# 16_-SP1_TYPEC_PWR_IN.net
KiCad netlist of a schematic drawn in Altium Designer
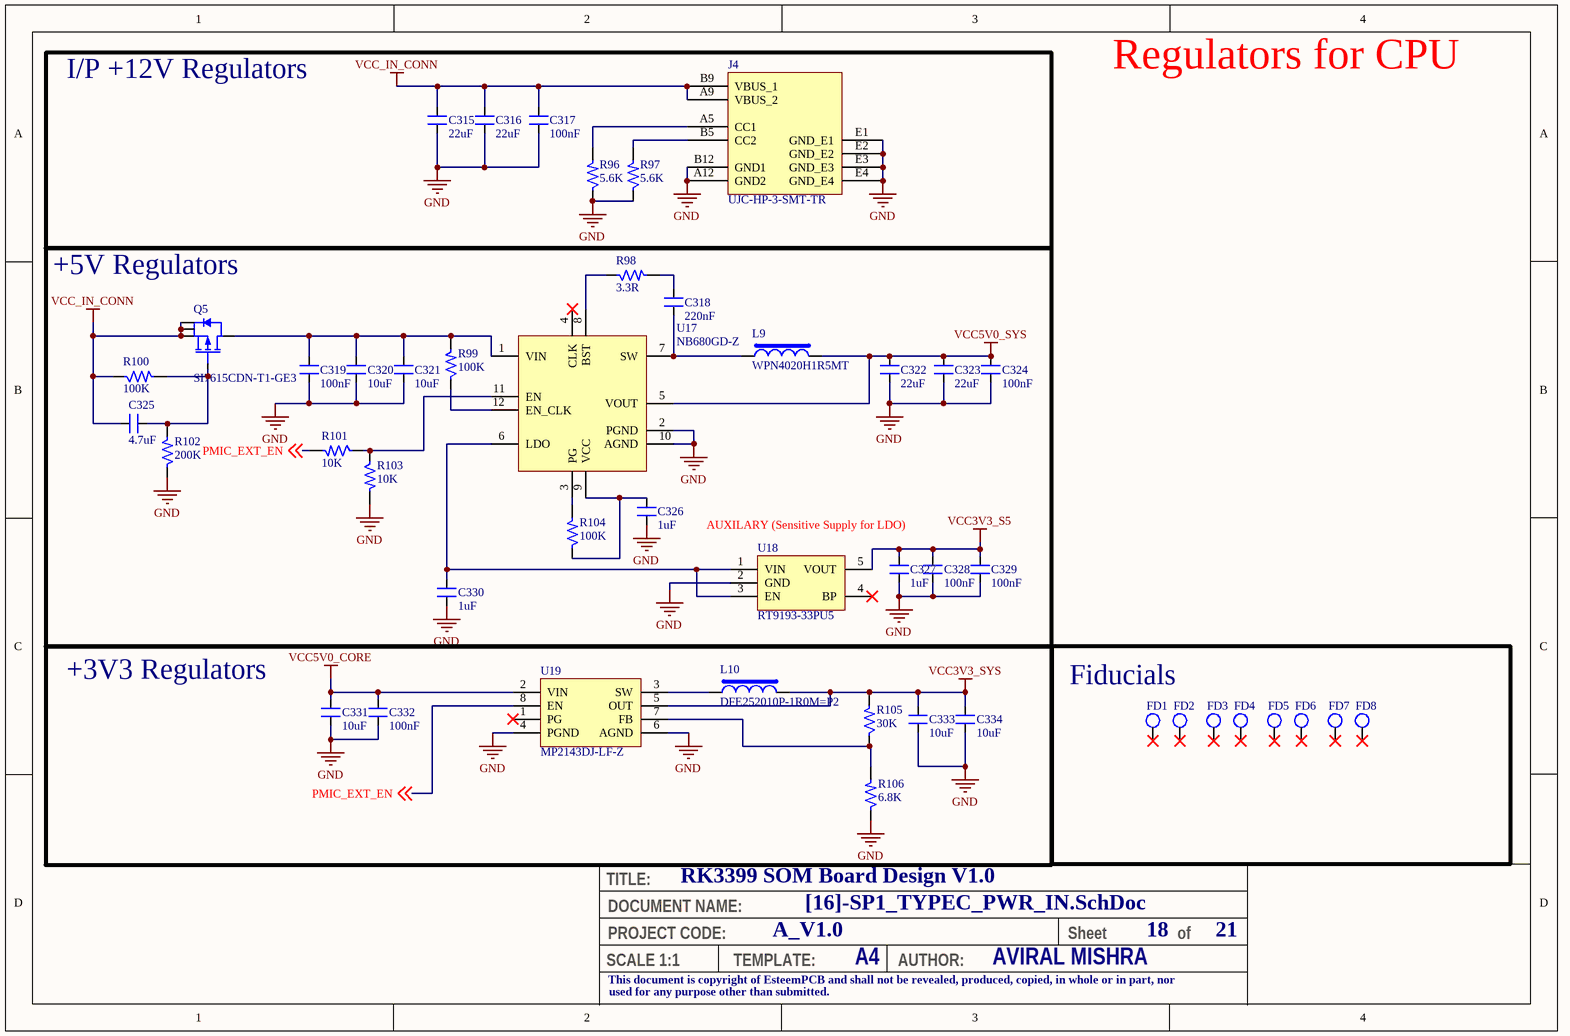
[diagram p0: [16]-SP1_TYPEC_PWR_IN.SchDoc]

(export (version "E")
  (design (tool "Eeschema 10.0.6"))
  (components
    (comp (ref "C315")
      (value "22uF")
      (footprint "CAP_0603")
      (description "22µF ±20% 10V Ceramic Capacitor X5R 0603 (1608 Metric)")
      (fields
        (field (name "MANUFACTURER") "Murata Electronics")
        (field (name "MANUFACTURER PART NUMBER") "GRM188R61A226ME15D")
      )
      (libsource (lib "RK3399 _Module_Schlib") (part "CAP_22uF-10V-20%-0603"))
    )
    (comp (ref "C316")
      (value "22uF")
      (footprint "CAP_0603")
      (description "22µF ±20% 10V Ceramic Capacitor X5R 0603 (1608 Metric)")
      (fields
        (field (name "MANUFACTURER") "Murata Electronics")
        (field (name "MANUFACTURER PART NUMBER") "GRM188R61A226ME15D")
      )
      (libsource (lib "RK3399 _Module_Schlib") (part "CAP_22uF-10V-20%-0603"))
    )
    (comp (ref "C317")
      (value "100nF")
      (footprint "CAP_0402")
      (description "0.1µF ±10% 25V Ceramic Capacitor X7R 0402 (1005 Metric)")
      (fields
        (field (name "MANUFACTURER") "Walsin Technology Corporation")
        (field (name "MANUFACTURER PART NUMBER") "0402B104K250CT")
      )
      (libsource (lib "RK3399 _Module_Schlib") (part "CAP_100nF-25V-10%-0402"))
    )
    (comp (ref "C318")
      (value "220nF")
      (footprint "CAP_0402")
      (description "0.22µF ±10% 10V Ceramic Capacitor X7R 0402 (1005 Metric)")
      (fields
        (field (name "MANUFACTURER") "Samsung Electro-Mechanics")
        (field (name "MANUFACTURER PART NUMBER") "CL05B224KP5NNNC")
      )
      (libsource (lib "RK3399 _Module_Schlib") (part "CAP_220nF-10V-10%-0402"))
    )
    (comp (ref "C319")
      (value "100nF")
      (footprint "CAP_0402")
      (description "0.1µF ±10% 25V Ceramic Capacitor X7R 0402 (1005 Metric)")
      (fields
        (field (name "MANUFACTURER") "Walsin Technology Corporation")
        (field (name "MANUFACTURER PART NUMBER") "0402B104K250CT")
      )
      (libsource (lib "RK3399 _Module_Schlib") (part "CAP_100nF-25V-10%-0402"))
    )
    (comp (ref "C320")
      (value "10uF")
      (footprint "CAP_0402")
      (description "10µF ±20% 10V Ceramic Capacitor X5R 0402 (1005 Metric)")
      (fields
        (field (name "MANUFACTURER PART NUMBER") "CL05A106MP5NUNC")
        (field (name "MANUFACTURER") "Samsung Electro-Mechanics")
      )
      (libsource (lib "RK3399 _Module_Schlib") (part "CAP_10uF-10V-20%-0402"))
    )
    (comp (ref "C321")
      (value "10uF")
      (footprint "CAP_0402")
      (description "10µF ±20% 10V Ceramic Capacitor X5R 0402 (1005 Metric)")
      (fields
        (field (name "MANUFACTURER PART NUMBER") "CL05A106MP5NUNC")
        (field (name "MANUFACTURER") "Samsung Electro-Mechanics")
      )
      (libsource (lib "RK3399 _Module_Schlib") (part "CAP_10uF-10V-20%-0402"))
    )
    (comp (ref "C322")
      (value "22uF")
      (footprint "CAP_0603")
      (description "22µF ±20% 10V Ceramic Capacitor X5R 0603 (1608 Metric)")
      (fields
        (field (name "MANUFACTURER") "Murata Electronics")
        (field (name "MANUFACTURER PART NUMBER") "GRM188R61A226ME15D")
      )
      (libsource (lib "RK3399 _Module_Schlib") (part "CAP_22uF-10V-20%-0603"))
    )
    (comp (ref "C323")
      (value "22uF")
      (footprint "CAP_0603")
      (description "22µF ±20% 10V Ceramic Capacitor X5R 0603 (1608 Metric)")
      (fields
        (field (name "MANUFACTURER") "Murata Electronics")
        (field (name "MANUFACTURER PART NUMBER") "GRM188R61A226ME15D")
      )
      (libsource (lib "RK3399 _Module_Schlib") (part "CAP_22uF-10V-20%-0603"))
    )
    (comp (ref "C324")
      (value "100nF")
      (footprint "CAP_0402")
      (description "0.1µF ±10% 25V Ceramic Capacitor X7R 0402 (1005 Metric)")
      (fields
        (field (name "MANUFACTURER") "Walsin Technology Corporation")
        (field (name "MANUFACTURER PART NUMBER") "0402B104K250CT")
      )
      (libsource (lib "RK3399 _Module_Schlib") (part "CAP_100nF-25V-10%-0402"))
    )
    (comp (ref "C325")
      (value "4.7uF")
      (footprint "CAP_0402")
      (description "4.7µF ±10% 10V Ceramic Capacitor X5R 0402 (1005 Metric)")
      (fields
        (field (name "MANUFACTURER") "Samsung Electro-Mechanics")
        (field (name "MANUFACTURER PART NUMBER") "CL05A475KP5NRNC")
      )
      (libsource (lib "RK3399 _Module_Schlib") (part "CAP_4.7uF-10V-10%-0402"))
    )
    (comp (ref "C326")
      (value "1uF")
      (footprint "CAP_0402")
      (description "1µF ±10% 16V Ceramic Capacitor X5R 0402 (1005 Metric)")
      (fields
        (field (name "MANUFACTURER") "Knowles Novacap")
        (field (name "MANUFACTURER PART NUMBER") "0402BW105K160YT")
      )
      (libsource (lib "RK3399 _Module_Schlib") (part "CAP_1uF-16V-10%-0402"))
    )
    (comp (ref "C327")
      (value "1uF")
      (footprint "CAP_0402")
      (description "1µF ±10% 16V Ceramic Capacitor X5R 0402 (1005 Metric)")
      (fields
        (field (name "MANUFACTURER") "Knowles Novacap")
        (field (name "MANUFACTURER PART NUMBER") "0402BW105K160YT")
      )
      (libsource (lib "RK3399 _Module_Schlib") (part "CAP_1uF-16V-10%-0402"))
    )
    (comp (ref "C328")
      (value "100nF")
      (footprint "CAP_0402")
      (description "0.1µF ±10% 25V Ceramic Capacitor X7R 0402 (1005 Metric)")
      (fields
        (field (name "MANUFACTURER") "Walsin Technology Corporation")
        (field (name "MANUFACTURER PART NUMBER") "0402B104K250CT")
      )
      (libsource (lib "RK3399 _Module_Schlib") (part "CAP_100nF-25V-10%-0402"))
    )
    (comp (ref "C329")
      (value "100nF")
      (footprint "CAP_0402")
      (description "0.1µF ±10% 25V Ceramic Capacitor X7R 0402 (1005 Metric)")
      (fields
        (field (name "MANUFACTURER") "Walsin Technology Corporation")
        (field (name "MANUFACTURER PART NUMBER") "0402B104K250CT")
      )
      (libsource (lib "RK3399 _Module_Schlib") (part "CAP_100nF-25V-10%-0402"))
    )
    (comp (ref "C330")
      (value "1uF")
      (footprint "CAP_0402")
      (description "1µF ±10% 16V Ceramic Capacitor X5R 0402 (1005 Metric)")
      (fields
        (field (name "MANUFACTURER") "Knowles Novacap")
        (field (name "MANUFACTURER PART NUMBER") "0402BW105K160YT")
      )
      (libsource (lib "RK3399 _Module_Schlib") (part "CAP_1uF-16V-10%-0402"))
    )
    (comp (ref "C331")
      (value "10uF")
      (footprint "CAP_0402")
      (description "10µF ±20% 10V Ceramic Capacitor X5R 0402 (1005 Metric)")
      (fields
        (field (name "MANUFACTURER PART NUMBER") "CL05A106MP5NUNC")
        (field (name "MANUFACTURER") "Samsung Electro-Mechanics")
      )
      (libsource (lib "RK3399 _Module_Schlib") (part "CAP_10uF-10V-20%-0402"))
    )
    (comp (ref "C332")
      (value "100nF")
      (footprint "CAP_0402")
      (description "0.1µF ±10% 25V Ceramic Capacitor X7R 0402 (1005 Metric)")
      (fields
        (field (name "MANUFACTURER") "Walsin Technology Corporation")
        (field (name "MANUFACTURER PART NUMBER") "0402B104K250CT")
      )
      (libsource (lib "RK3399 _Module_Schlib") (part "CAP_100nF-25V-10%-0402"))
    )
    (comp (ref "C333")
      (value "10uF")
      (footprint "CAP_0402")
      (description "10µF ±20% 10V Ceramic Capacitor X5R 0402 (1005 Metric)")
      (fields
        (field (name "MANUFACTURER PART NUMBER") "CL05A106MP5NUNC")
        (field (name "MANUFACTURER") "Samsung Electro-Mechanics")
      )
      (libsource (lib "RK3399 _Module_Schlib") (part "CAP_10uF-10V-20%-0402"))
    )
    (comp (ref "C334")
      (value "10uF")
      (footprint "CAP_0402")
      (description "10µF ±20% 10V Ceramic Capacitor X5R 0402 (1005 Metric)")
      (fields
        (field (name "MANUFACTURER PART NUMBER") "CL05A106MP5NUNC")
        (field (name "MANUFACTURER") "Samsung Electro-Mechanics")
      )
      (libsource (lib "RK3399 _Module_Schlib") (part "CAP_10uF-10V-20%-0402"))
    )
    (comp (ref "FD1")
      (value "Fiducial")
      (footprint "FIDUCIAL_78.7MIL")
      (description "78.7mil Fiducials SMD")
      (fields (field (name "MANUFACTURER") "NA") (field (name "NYMBLE PART NUMBER") "1EA-AA-0523"))
      (libsource (lib "RK3399 _Module_Intlib") (part "Fiducials_78.7mil"))
    )
    (comp (ref "FD2")
      (value "Fiducial")
      (footprint "FIDUCIAL_78.7MIL")
      (description "78.7mil Fiducials SMD")
      (fields (field (name "MANUFACTURER") "NA") (field (name "NYMBLE PART NUMBER") "1EA-AA-0523"))
      (libsource (lib "RK3399 _Module_Intlib") (part "Fiducials_78.7mil"))
    )
    (comp (ref "FD3")
      (value "Fiducial")
      (footprint "FIDUCIAL_78.7MIL")
      (description "78.7mil Fiducials SMD")
      (fields (field (name "MANUFACTURER") "NA") (field (name "NYMBLE PART NUMBER") "1EA-AA-0523"))
      (libsource (lib "RK3399 _Module_Intlib") (part "Fiducials_78.7mil"))
    )
    (comp (ref "FD4")
      (value "Fiducial")
      (footprint "FIDUCIAL_78.7MIL")
      (description "78.7mil Fiducials SMD")
      (fields (field (name "MANUFACTURER") "NA") (field (name "NYMBLE PART NUMBER") "1EA-AA-0523"))
      (libsource (lib "RK3399 _Module_Intlib") (part "Fiducials_78.7mil"))
    )
    (comp (ref "FD5")
      (value "Fiducial")
      (footprint "FIDUCIAL_78.7MIL")
      (description "78.7mil Fiducials SMD")
      (fields (field (name "MANUFACTURER") "NA") (field (name "NYMBLE PART NUMBER") "1EA-AA-0523"))
      (libsource (lib "RK3399 _Module_Intlib") (part "Fiducials_78.7mil"))
    )
    (comp (ref "FD6")
      (value "Fiducial")
      (footprint "FIDUCIAL_78.7MIL")
      (description "78.7mil Fiducials SMD")
      (fields (field (name "MANUFACTURER") "NA") (field (name "NYMBLE PART NUMBER") "1EA-AA-0523"))
      (libsource (lib "RK3399 _Module_Intlib") (part "Fiducials_78.7mil"))
    )
    (comp (ref "FD7")
      (value "Fiducial")
      (footprint "FIDUCIAL_78.7MIL")
      (description "78.7mil Fiducials SMD")
      (fields (field (name "MANUFACTURER") "NA") (field (name "NYMBLE PART NUMBER") "1EA-AA-0523"))
      (libsource (lib "RK3399 _Module_Intlib") (part "Fiducials_78.7mil"))
    )
    (comp (ref "FD8")
      (value "Fiducial")
      (footprint "FIDUCIAL_78.7MIL")
      (description "78.7mil Fiducials SMD")
      (fields (field (name "MANUFACTURER") "NA") (field (name "NYMBLE PART NUMBER") "1EA-AA-0523"))
      (libsource (lib "RK3399 _Module_Intlib") (part "Fiducials_78.7mil"))
    )
    (comp (ref "J4")
      (value "UJC-HP-3-SMT-TR")
      (footprint "CON6_48.4_UJC-HP-3-SMT-TR")
      (fields (field (name "MANUFACTURER") "CUI Devices"))
      (libsource (lib "RK3399 _Module_Schlib") (part "CON-TYPEC_6X1-100-RA-TH"))
    )
    (comp (ref "L9")
      (value "WPN4020H1R5MT")
      (footprint "IND_1616")
      (fields (field (name "MANUFACTURER") "Sunlord"))
      (libsource (lib "RK3399 _Module_Schlib") (part "IND_1.5uH-6A-20%-SMD"))
    )
    (comp (ref "L10")
      (value "DFE252010P-1R0M=P2")
      (footprint "IND_1008")
      (description "1µH Shielded Wirewound Inductor 3.8A 54mOhm Max 1008 (2520 Metric)")
      (fields (field (name "MANUFACTURER") "Murata Electronics"))
      (libsource (lib "RK3399 _Module_Schlib") (part "IND_1uH-3.8A-20%-1008"))
    )
    (comp (ref "Q5")
      (value "SI7615CDN-T1-GE3")
      (footprint "PowerPAK_1212-8_SMD")
      (description "P-Channel 20V 35A (Tc) 33W (Tc) Surface Mount PowerPAK® 1212-8")
      (fields (field (name "MANUFACTURER") "Vishay Siliconix"))
      (libsource (lib "RK3399 _Module_Schlib") (part "MOSFET-P_20V-35A-1212-8"))
    )
    (comp (ref "R96")
      (value "5.6K")
      (footprint "RES_0402")
      (fields
        (field (name "MANUFACTURER") "KOA Speer Electronics, Inc.")
        (field (name "MANUFACTURER PART NUMBER") "RK73H1ETTP5601F")
      )
      (libsource (lib "RK3399 _Module_Schlib") (part "RES_5.6K-0.1W-1%-0402"))
    )
    (comp (ref "R97")
      (value "5.6K")
      (footprint "RES_0402")
      (fields
        (field (name "MANUFACTURER") "KOA Speer Electronics, Inc.")
        (field (name "MANUFACTURER PART NUMBER") "RK73H1ETTP5601F")
      )
      (libsource (lib "RK3399 _Module_Schlib") (part "RES_5.6K-0.1W-1%-0402"))
    )
    (comp (ref "R98")
      (value "3.3R")
      (footprint "RES_0402")
      (fields
        (field (name "MANUFACTURER") "Panasonic Electronic Components")
        (field (name "MANUFACTURER PART NUMBER") "ERJ-U02F3R30X")
      )
      (libsource (lib "RK3399 _Module_Schlib") (part "RES_3.3R-0.1W-1%-0402"))
    )
    (comp (ref "R99")
      (value "100K")
      (footprint "RES_0402")
      (description "100 kOhms ±1% 0.1W, 1/10W Chip Resistor 0402 (1005 Metric) Anti-Sulfur Thin Film")
      (fields
        (field (name "MANUFACTURER") "Vishay Beyschlag/Draloric/BC Components")
        (field (name "MANUFACTURER PART NUMBER") "MCS04020C1003FE000")
      )
      (libsource (lib "RK3399 _Module_Schlib") (part "RES_100K-0.1W-1%-0402"))
    )
    (comp (ref "R100")
      (value "100K")
      (footprint "RES_0402")
      (description "100 kOhms ±1% 0.1W, 1/10W Chip Resistor 0402 (1005 Metric) Anti-Sulfur Thin Film")
      (fields
        (field (name "MANUFACTURER") "Vishay Beyschlag/Draloric/BC Components")
        (field (name "MANUFACTURER PART NUMBER") "MCS04020C1003FE000")
      )
      (libsource (lib "RK3399 _Module_Schlib") (part "RES_100K-0.1W-1%-0402"))
    )
    (comp (ref "R101")
      (value "10K")
      (footprint "RES_0402")
      (description "10 kOhms ±1% 0.1W, 1/10W Chip Resistor 0402 (1005 Metric) Anti-Sulfur Thin Film")
      (fields
        (field (name "MANUFACTURER") "Vishay Beyschlag/Draloric/BC Components")
        (field (name "MANUFACTURER PART NUMBER") "MCS04020C1002FE000")
      )
      (libsource (lib "RK3399 _Module_Schlib") (part "RES_10K-0.1W-1%-0402"))
    )
    (comp (ref "R102")
      (value "200K")
      (footprint "RES_0402")
      (description "200 kOhms ±1% 0.1W, 1/10W Chip Resistor 0402 (1005 Metric) Automotive AEC-Q200 Thick Film")
      (fields
        (field (name "MANUFACTURER") "Panasonic Electronic Components")
        (field (name "MANUFACTURER PART NUMBER") "ERJ-2RKF2003X")
      )
      (libsource (lib "RK3399 _Module_Schlib") (part "RES_200K-0.1W-1%-0402"))
    )
    (comp (ref "R103")
      (value "10K")
      (footprint "RES_0402")
      (description "10 kOhms ±1% 0.1W, 1/10W Chip Resistor 0402 (1005 Metric) Anti-Sulfur Thin Film")
      (fields
        (field (name "MANUFACTURER") "Vishay Beyschlag/Draloric/BC Components")
        (field (name "MANUFACTURER PART NUMBER") "MCS04020C1002FE000")
      )
      (libsource (lib "RK3399 _Module_Schlib") (part "RES_10K-0.1W-1%-0402"))
    )
    (comp (ref "R104")
      (value "100K")
      (footprint "RES_0402")
      (description "100 kOhms ±1% 0.1W, 1/10W Chip Resistor 0402 (1005 Metric) Anti-Sulfur Thin Film")
      (fields
        (field (name "MANUFACTURER") "Vishay Beyschlag/Draloric/BC Components")
        (field (name "MANUFACTURER PART NUMBER") "MCS04020C1003FE000")
      )
      (libsource (lib "RK3399 _Module_Schlib") (part "RES_100K-0.1W-1%-0402"))
    )
    (comp (ref "R105")
      (value "30K")
      (footprint "RES_0402")
      (fields
        (field (name "MANUFACTURER") "KOA Speer Electronics, Inc.")
        (field (name "MANUFACTURER PART NUMBER") "RK73H1ETTP3002F")
      )
      (libsource (lib "RK3399 _Module_Schlib") (part "RES_30K-0.1W-1%-0402"))
    )
    (comp (ref "R106")
      (value "6.8K")
      (footprint "RES_0402")
      (description "6.8 kOhms ±1% 0.1W, 1/10W Chip Resistor 0402 (1005 Metric) Anti-Sulfur Thin Film")
      (fields
        (field (name "MANUFACTURER PART NUMBER") "MCS04020C6801FE000")
        (field (name "MANUFACTURER") "Vishay Beyschlag/Draloric/BC Components")
      )
      (libsource (lib "RK3399 _Module_Schlib") (part "RES_6.8K-0.1W-1%-0402"))
    )
    (comp (ref "U17")
      (value "NB680GD-Z")
      (footprint "QFN-12_19_118X118_SMD")
      (description "Switching Voltage Regulators 26V Fixed 3.3 V-8A Sync Buck Converter")
      (fields (field (name "MANUFACTURER") "Monolithic Power Systems (MPS)"))
      (libsource (lib "RK3399 _Module_Schlib") (part "REG_3.3V-26V-8A-QFN-12"))
    )
    (comp (ref "U18")
      (value "RT9193-33PU5")
      (footprint "SC70-5")
      (description "SC-70-5 Dropout Regulators(LDO) RoHS")
      (fields (field (name "MANUFACTURER") "Richtek Tech"))
      (libsource (lib "RK3399 _Module_Schlib") (part "REG_3.3V-5.5V-300mA-SC-70-5"))
    )
    (comp (ref "U19")
      (value "MP2143DJ-LF-Z")
      (footprint "SOT23-8")
      (description "Switching Voltage Regulators 3A, 5.5V, 1.2MHz Sync Stp-Dwn Swtchr")
      (fields (field (name "MANUFACTURER") "Monolithic Power Systems (MPS)"))
      (libsource (lib "RK3399 _Module_Schlib") (part "REG_0.6~5V-5.5V-3A-TSOT-23-8"))
    )
  )
  (nets
    (net (code "1") (name "GND") (class "Default")
      (node (ref "C315") (pin "1") (pinfunction "1_1") (pintype "passive"))
      (node (ref "C316") (pin "1") (pinfunction "1_1") (pintype "passive"))
      (node (ref "C317") (pin "1") (pinfunction "1_1") (pintype "passive"))
      (node (ref "C319") (pin "1") (pinfunction "1_1") (pintype "passive"))
      (node (ref "C320") (pin "1") (pinfunction "1_1") (pintype "passive"))
      (node (ref "C321") (pin "1") (pinfunction "1_1") (pintype "passive"))
      (node (ref "C322") (pin "1") (pinfunction "1_1") (pintype "passive"))
      (node (ref "C323") (pin "1") (pinfunction "1_1") (pintype "passive"))
      (node (ref "C324") (pin "1") (pinfunction "1_1") (pintype "passive"))
      (node (ref "C326") (pin "1") (pinfunction "1_1") (pintype "passive"))
      (node (ref "C327") (pin "1") (pinfunction "1_1") (pintype "passive"))
      (node (ref "C328") (pin "1") (pinfunction "1_1") (pintype "passive"))
      (node (ref "C329") (pin "1") (pinfunction "1_1") (pintype "passive"))
      (node (ref "C330") (pin "1") (pinfunction "1_1") (pintype "passive"))
      (node (ref "C331") (pin "1") (pinfunction "1_1") (pintype "passive"))
      (node (ref "C332") (pin "1") (pinfunction "1_1") (pintype "passive"))
      (node (ref "C333") (pin "1") (pinfunction "1_1") (pintype "passive"))
      (node (ref "C334") (pin "1") (pinfunction "1_1") (pintype "passive"))
      (node (ref "J4") (pin "A12") (pinfunction "GND2_A12") (pintype "passive"))
      (node (ref "J4") (pin "B12") (pinfunction "GND1_B12") (pintype "passive"))
      (node (ref "J4") (pin "E1") (pinfunction "GND_E1_E1") (pintype "passive"))
      (node (ref "J4") (pin "E2") (pinfunction "GND_E2_E2") (pintype "passive"))
      (node (ref "J4") (pin "E3") (pinfunction "GND_E3_E3") (pintype "passive"))
      (node (ref "J4") (pin "E4") (pinfunction "GND_E4_E4") (pintype "passive"))
      (node (ref "R102") (pin "1") (pinfunction "1_1") (pintype "passive"))
      (node (ref "R103") (pin "2") (pinfunction "2_2") (pintype "passive"))
      (node (ref "R106") (pin "1") (pinfunction "1_1") (pintype "passive"))
      (node (ref "R96") (pin "1") (pinfunction "1_1") (pintype "passive"))
      (node (ref "R97") (pin "1") (pinfunction "1_1") (pintype "passive"))
      (node (ref "U17") (pin "10") (pinfunction "AGND_10") (pintype "passive"))
      (node (ref "U17") (pin "2") (pinfunction "PGND_2") (pintype "passive"))
      (node (ref "U18") (pin "2") (pinfunction "GND_2") (pintype "passive"))
      (node (ref "U19") (pin "4") (pinfunction "PGND_4") (pintype "passive"))
      (node (ref "U19") (pin "6") (pinfunction "AGND_6") (pintype "passive"))
    )
    (net (code "2") (name "Net-(C318-Pad2)") (class "Default")
      (node (ref "C318") (pin "2") (pinfunction "2_2") (pintype "passive"))
      (node (ref "R98") (pin "2") (pinfunction "2_2") (pintype "passive"))
    )
    (net (code "3") (name "Net-(J4-CC1)") (class "Default")
      (node (ref "J4") (pin "A5") (pinfunction "CC1_A5") (pintype "passive"))
      (node (ref "R96") (pin "2") (pinfunction "2_2") (pintype "passive"))
    )
    (net (code "4") (name "Net-(J4-CC2)") (class "Default")
      (node (ref "J4") (pin "B5") (pinfunction "CC2_B5") (pintype "passive"))
      (node (ref "R97") (pin "2") (pinfunction "2_2") (pintype "passive"))
    )
    (net (code "5") (name "Net-(Q5-D)") (class "Default")
      (node (ref "C319") (pin "2") (pinfunction "2_2") (pintype "passive"))
      (node (ref "C320") (pin "2") (pinfunction "2_2") (pintype "passive"))
      (node (ref "C321") (pin "2") (pinfunction "2_2") (pintype "passive"))
      (node (ref "Q5") (pin "5") (pinfunction "D_5") (pintype "passive"))
      (node (ref "R99") (pin "2") (pinfunction "2_2") (pintype "passive"))
      (node (ref "U17") (pin "1") (pinfunction "VIN_1") (pintype "passive"))
    )
    (net (code "6") (name "Net-(Q5-G)") (class "Default")
      (node (ref "C325") (pin "2") (pinfunction "2_2") (pintype "passive"))
      (node (ref "Q5") (pin "4") (pinfunction "G_4") (pintype "passive"))
      (node (ref "R100") (pin "2") (pinfunction "2_2") (pintype "passive"))
      (node (ref "R102") (pin "2") (pinfunction "2_2") (pintype "passive"))
    )
    (net (code "7") (name "Net-(U17-BST)") (class "Default")
      (node (ref "R98") (pin "1") (pinfunction "1_1") (pintype "passive"))
      (node (ref "U17") (pin "8") (pinfunction "BST_8") (pintype "passive"))
    )
    (net (code "8") (name "Net-(U17-EN)") (class "Default")
      (node (ref "R101") (pin "1") (pinfunction "1_1") (pintype "passive"))
      (node (ref "R103") (pin "1") (pinfunction "1_1") (pintype "passive"))
      (node (ref "U17") (pin "11") (pinfunction "EN_11") (pintype "passive"))
    )
    (net (code "9") (name "Net-(U17-EN_CLK)") (class "Default")
      (node (ref "R99") (pin "1") (pinfunction "1_1") (pintype "passive"))
      (node (ref "U17") (pin "12") (pinfunction "EN_CLK_12") (pintype "passive"))
    )
    (net (code "10") (name "Net-(U17-LDO)") (class "Default")
      (node (ref "C330") (pin "2") (pinfunction "2_2") (pintype "passive"))
      (node (ref "U17") (pin "6") (pinfunction "LDO_6") (pintype "passive"))
      (node (ref "U18") (pin "1") (pinfunction "VIN_1") (pintype "passive"))
      (node (ref "U18") (pin "3") (pinfunction "EN_3") (pintype "passive"))
    )
    (net (code "11") (name "Net-(U17-PG)") (class "Default")
      (node (ref "R104") (pin "2") (pinfunction "2_2") (pintype "passive"))
      (node (ref "U17") (pin "3") (pinfunction "PG_3") (pintype "passive"))
    )
    (net (code "12") (name "Net-(U17-SW)") (class "Default")
      (node (ref "C318") (pin "1") (pinfunction "1_1") (pintype "passive"))
      (node (ref "L9") (pin "1") (pinfunction "1_1") (pintype "passive"))
      (node (ref "U17") (pin "7") (pinfunction "SW_7") (pintype "passive"))
    )
    (net (code "13") (name "Net-(U17-VCC)") (class "Default")
      (node (ref "C326") (pin "2") (pinfunction "2_2") (pintype "passive"))
      (node (ref "R104") (pin "1") (pinfunction "1_1") (pintype "passive"))
      (node (ref "U17") (pin "9") (pinfunction "VCC_9") (pintype "passive"))
    )
    (net (code "14") (name "Net-(U19-FB)") (class "Default")
      (node (ref "R105") (pin "1") (pinfunction "1_1") (pintype "passive"))
      (node (ref "R106") (pin "2") (pinfunction "2_2") (pintype "passive"))
      (node (ref "U19") (pin "7") (pinfunction "FB_7") (pintype "passive"))
    )
    (net (code "15") (name "Net-(U19-SW)") (class "Default")
      (node (ref "L10") (pin "1") (pinfunction "1_1") (pintype "passive"))
      (node (ref "U19") (pin "3") (pinfunction "SW_3") (pintype "passive"))
    )
    (net (code "16") (name "PMIC_EXT_EN") (class "Default")
      (node (ref "R101") (pin "2") (pinfunction "2_2") (pintype "passive"))
      (node (ref "U19") (pin "8") (pinfunction "EN_8") (pintype "passive"))
    )
    (net (code "17") (name "VCC3V3_S5") (class "Default")
      (node (ref "C327") (pin "2") (pinfunction "2_2") (pintype "passive"))
      (node (ref "C328") (pin "2") (pinfunction "2_2") (pintype "passive"))
      (node (ref "C329") (pin "2") (pinfunction "2_2") (pintype "passive"))
      (node (ref "U18") (pin "5") (pinfunction "VOUT_5") (pintype "passive"))
    )
    (net (code "18") (name "VCC3V3_SYS") (class "Default")
      (node (ref "C333") (pin "2") (pinfunction "2_2") (pintype "passive"))
      (node (ref "C334") (pin "2") (pinfunction "2_2") (pintype "passive"))
      (node (ref "L10") (pin "2") (pinfunction "2_2") (pintype "passive"))
      (node (ref "R105") (pin "2") (pinfunction "2_2") (pintype "passive"))
      (node (ref "U19") (pin "5") (pinfunction "OUT_5") (pintype "passive"))
    )
    (net (code "19") (name "VCC5V0_CORE") (class "Default")
      (node (ref "C331") (pin "2") (pinfunction "2_2") (pintype "passive"))
      (node (ref "C332") (pin "2") (pinfunction "2_2") (pintype "passive"))
      (node (ref "U19") (pin "2") (pinfunction "VIN_2") (pintype "passive"))
    )
    (net (code "20") (name "VCC5V0_SYS") (class "Default")
      (node (ref "C322") (pin "2") (pinfunction "2_2") (pintype "passive"))
      (node (ref "C323") (pin "2") (pinfunction "2_2") (pintype "passive"))
      (node (ref "C324") (pin "2") (pinfunction "2_2") (pintype "passive"))
      (node (ref "L9") (pin "2") (pinfunction "2_2") (pintype "passive"))
      (node (ref "U17") (pin "5") (pinfunction "VOUT_5") (pintype "passive"))
    )
    (net (code "21") (name "VCC_IN_CONN") (class "Default")
      (node (ref "C315") (pin "2") (pinfunction "2_2") (pintype "passive"))
      (node (ref "C316") (pin "2") (pinfunction "2_2") (pintype "passive"))
      (node (ref "C317") (pin "2") (pinfunction "2_2") (pintype "passive"))
      (node (ref "C325") (pin "1") (pinfunction "1_1") (pintype "passive"))
      (node (ref "J4") (pin "A9") (pinfunction "VBUS_2_A9") (pintype "passive"))
      (node (ref "J4") (pin "B9") (pinfunction "VBUS_1_B9") (pintype "passive"))
      (node (ref "Q5") (pin "1") (pinfunction "S_1") (pintype "passive"))
      (node (ref "Q5") (pin "2") (pinfunction "S_2") (pintype "passive"))
      (node (ref "Q5") (pin "3") (pinfunction "S_3") (pintype "passive"))
      (node (ref "R100") (pin "1") (pinfunction "1_1") (pintype "passive"))
    )
    (net (code "22") (name "unconnected-(FD1-Pad1)") (class "Default")
      (node (ref "FD1") (pin "1") (pinfunction "1_1") (pintype "passive+no_connect"))
    )
    (net (code "23") (name "unconnected-(FD2-Pad1)") (class "Default")
      (node (ref "FD2") (pin "1") (pinfunction "1_1") (pintype "passive+no_connect"))
    )
    (net (code "24") (name "unconnected-(FD3-Pad1)") (class "Default")
      (node (ref "FD3") (pin "1") (pinfunction "1_1") (pintype "passive+no_connect"))
    )
    (net (code "25") (name "unconnected-(FD4-Pad1)") (class "Default")
      (node (ref "FD4") (pin "1") (pinfunction "1_1") (pintype "passive+no_connect"))
    )
    (net (code "26") (name "unconnected-(FD5-Pad1)") (class "Default")
      (node (ref "FD5") (pin "1") (pinfunction "1_1") (pintype "passive+no_connect"))
    )
    (net (code "27") (name "unconnected-(FD6-Pad1)") (class "Default")
      (node (ref "FD6") (pin "1") (pinfunction "1_1") (pintype "passive+no_connect"))
    )
    (net (code "28") (name "unconnected-(FD7-Pad1)") (class "Default")
      (node (ref "FD7") (pin "1") (pinfunction "1_1") (pintype "passive+no_connect"))
    )
    (net (code "29") (name "unconnected-(FD8-Pad1)") (class "Default")
      (node (ref "FD8") (pin "1") (pinfunction "1_1") (pintype "passive+no_connect"))
    )
    (net (code "30") (name "unconnected-(U17-CLK-Pad4)") (class "Default")
      (node (ref "U17") (pin "4") (pinfunction "CLK_4") (pintype "passive+no_connect"))
    )
    (net (code "31") (name "unconnected-(U18-BP-Pad4)") (class "Default")
      (node (ref "U18") (pin "4") (pinfunction "BP_4") (pintype "passive+no_connect"))
    )
    (net (code "32") (name "unconnected-(U19-PG-Pad1)") (class "Default")
      (node (ref "U19") (pin "1") (pinfunction "PG_1") (pintype "passive+no_connect"))
    )
  )
)
